# 3x3Bottom.net
KiCad netlist of a schematic drawn in EAGLE
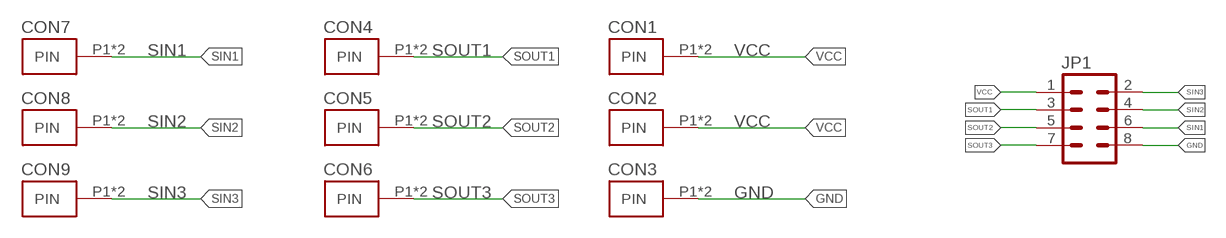
[diagram p0: schematic, sheet 1]

(export (version "E")
  (design (tool "Eeschema 10.0.6"))
  (components
    (comp (ref "CON1")
      (value "SHIELD_FINGER0820")
      (footprint "eagle-import:SHIELD_FINGER_PKG")
      (libsource (lib "eagle-import") (part "SHIELD_FINGER0820"))
    )
    (comp (ref "CON2")
      (value "SHIELD_FINGER0820")
      (footprint "eagle-import:SHIELD_FINGER_PKG")
      (libsource (lib "eagle-import") (part "SHIELD_FINGER0820"))
    )
    (comp (ref "CON3")
      (value "SHIELD_FINGER0820")
      (footprint "eagle-import:SHIELD_FINGER_PKG")
      (libsource (lib "eagle-import") (part "SHIELD_FINGER0820"))
    )
    (comp (ref "CON4")
      (value "SHIELD_FINGER0820")
      (footprint "eagle-import:SHIELD_FINGER_PKG")
      (libsource (lib "eagle-import") (part "SHIELD_FINGER0820"))
    )
    (comp (ref "CON5")
      (value "SHIELD_FINGER0820")
      (footprint "eagle-import:SHIELD_FINGER_PKG")
      (libsource (lib "eagle-import") (part "SHIELD_FINGER0820"))
    )
    (comp (ref "CON6")
      (value "SHIELD_FINGER0820")
      (footprint "eagle-import:SHIELD_FINGER_PKG")
      (libsource (lib "eagle-import") (part "SHIELD_FINGER0820"))
    )
    (comp (ref "CON7")
      (value "SHIELD_FINGER0820")
      (footprint "eagle-import:SHIELD_FINGER_PKG")
      (libsource (lib "eagle-import") (part "SHIELD_FINGER0820"))
    )
    (comp (ref "CON8")
      (value "SHIELD_FINGER0820")
      (footprint "eagle-import:SHIELD_FINGER_PKG")
      (libsource (lib "eagle-import") (part "SHIELD_FINGER0820"))
    )
    (comp (ref "CON9")
      (value "SHIELD_FINGER0820")
      (footprint "eagle-import:SHIELD_FINGER_PKG")
      (libsource (lib "eagle-import") (part "SHIELD_FINGER0820"))
    )
    (comp (ref "JP1")
      (value "M04X2_0.1\"")
      (footprint "eagle-import:M04X2_0.1__PADS")
      (libsource (lib "eagle-import") (part "M04X2_0.1{dblquote}"))
    )
  )
  (nets
    (net (code "1") (name "GND") (class "Default")
      (node (ref "CON3") (pin "P1") (pinfunction "PIN_P1") (pintype "bidirectional"))
      (node (ref "CON3") (pin "P2") (pinfunction "PIN_P2") (pintype "bidirectional"))
      (node (ref "JP1") (pin "8") (pinfunction "8_8") (pintype "passive"))
    )
    (net (code "2") (name "SIN1") (class "Default")
      (node (ref "CON7") (pin "P1") (pinfunction "PIN_P1") (pintype "bidirectional"))
      (node (ref "CON7") (pin "P2") (pinfunction "PIN_P2") (pintype "bidirectional"))
      (node (ref "JP1") (pin "6") (pinfunction "6_6") (pintype "passive"))
    )
    (net (code "3") (name "SIN2") (class "Default")
      (node (ref "CON8") (pin "P1") (pinfunction "PIN_P1") (pintype "bidirectional"))
      (node (ref "CON8") (pin "P2") (pinfunction "PIN_P2") (pintype "bidirectional"))
      (node (ref "JP1") (pin "4") (pinfunction "4_4") (pintype "passive"))
    )
    (net (code "4") (name "SIN3") (class "Default")
      (node (ref "CON9") (pin "P1") (pinfunction "PIN_P1") (pintype "bidirectional"))
      (node (ref "CON9") (pin "P2") (pinfunction "PIN_P2") (pintype "bidirectional"))
      (node (ref "JP1") (pin "2") (pinfunction "2_2") (pintype "passive"))
    )
    (net (code "5") (name "SOUT1") (class "Default")
      (node (ref "CON4") (pin "P1") (pinfunction "PIN_P1") (pintype "bidirectional"))
      (node (ref "CON4") (pin "P2") (pinfunction "PIN_P2") (pintype "bidirectional"))
      (node (ref "JP1") (pin "3") (pinfunction "3_3") (pintype "passive"))
    )
    (net (code "6") (name "SOUT2") (class "Default")
      (node (ref "CON5") (pin "P1") (pinfunction "PIN_P1") (pintype "bidirectional"))
      (node (ref "CON5") (pin "P2") (pinfunction "PIN_P2") (pintype "bidirectional"))
      (node (ref "JP1") (pin "5") (pinfunction "5_5") (pintype "passive"))
    )
    (net (code "7") (name "SOUT3") (class "Default")
      (node (ref "CON6") (pin "P1") (pinfunction "PIN_P1") (pintype "bidirectional"))
      (node (ref "CON6") (pin "P2") (pinfunction "PIN_P2") (pintype "bidirectional"))
      (node (ref "JP1") (pin "7") (pinfunction "7_7") (pintype "passive"))
    )
    (net (code "8") (name "VCC") (class "Default")
      (node (ref "CON1") (pin "P1") (pinfunction "PIN_P1") (pintype "bidirectional"))
      (node (ref "CON1") (pin "P2") (pinfunction "PIN_P2") (pintype "bidirectional"))
      (node (ref "CON2") (pin "P1") (pinfunction "PIN_P1") (pintype "bidirectional"))
      (node (ref "CON2") (pin "P2") (pinfunction "PIN_P2") (pintype "bidirectional"))
      (node (ref "JP1") (pin "1") (pinfunction "1_1") (pintype "passive"))
    )
  )
)
